# ATmega_Motherboard.net
KiCad netlist of a schematic drawn in Altium Designer
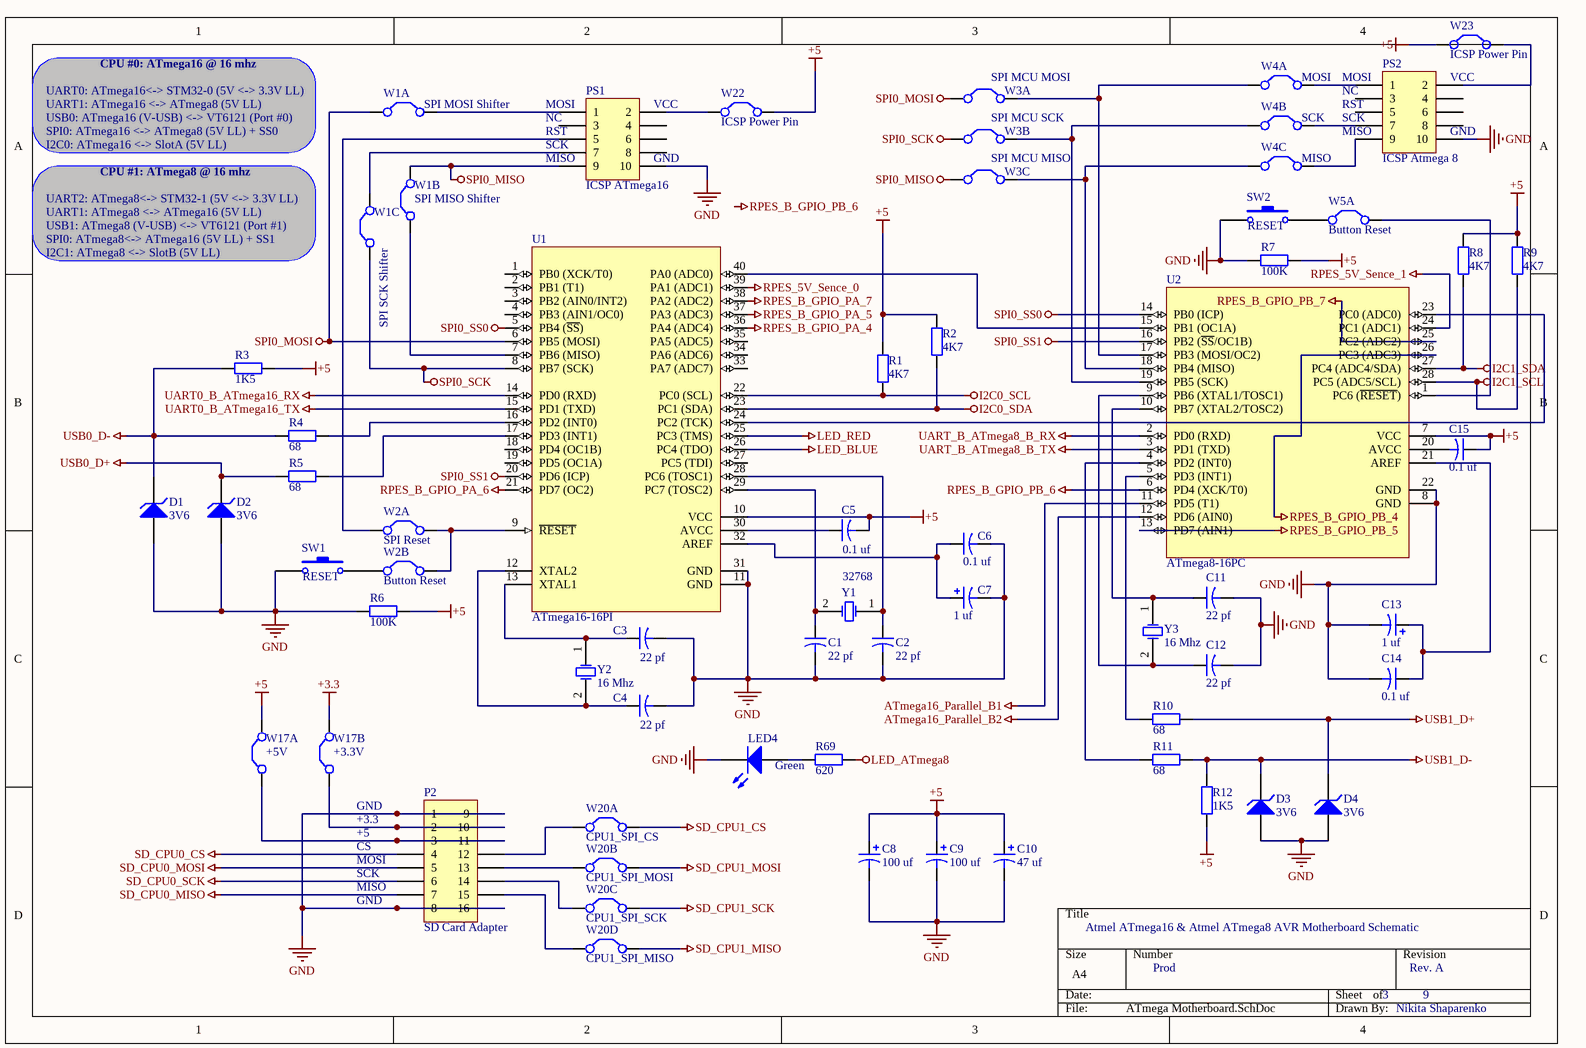
[diagram p0: ATmega Motherboard.SchDoc]

(export (version "E")
  (design (tool "Eeschema 10.0.6"))
  (components
    (comp (ref "C1")
      (value "22 pf")
      (footprint "CAPR5-4X5")
      (description "Capacitor")
      (fields (field (name "Comment") "Cap2") (field (name "PUBLISHER") "Altium Limited"))
      (libsource (lib "Miscellaneous Devices") (part "Cap2"))
    )
    (comp (ref "C2")
      (value "22 pf")
      (footprint "CAPR5-4X5")
      (description "Capacitor")
      (fields (field (name "Comment") "Cap2") (field (name "PUBLISHER") "Altium Limited"))
      (libsource (lib "Miscellaneous Devices") (part "Cap2"))
    )
    (comp (ref "C3")
      (value "22 pf")
      (footprint "CAPR5-4X5")
      (description "Capacitor")
      (fields (field (name "Comment") "Cap2") (field (name "PUBLISHER") "Altium Limited"))
      (libsource (lib "Miscellaneous Devices") (part "Cap2"))
    )
    (comp (ref "C4")
      (value "22 pf")
      (footprint "CAPR5-4X5")
      (description "Capacitor")
      (fields (field (name "Comment") "Cap2") (field (name "PUBLISHER") "Altium Limited"))
      (libsource (lib "Miscellaneous Devices") (part "Cap2"))
    )
    (comp (ref "C5")
      (value "0.1 uf")
      (footprint "CAPR5-4X5")
      (description "Capacitor")
      (fields (field (name "Comment") "Cap2") (field (name "PUBLISHER") "Altium Limited"))
      (libsource (lib "Miscellaneous Devices") (part "Cap2"))
    )
    (comp (ref "C6")
      (value "0.1 uf")
      (footprint "CAPR5-4X5")
      (description "Capacitor")
      (fields (field (name "Comment") "Cap2") (field (name "PUBLISHER") "Altium Limited"))
      (libsource (lib "Miscellaneous Devices") (part "Cap2"))
    )
    (comp (ref "C7")
      (value "1 uf")
      (footprint "RAD-0.2")
      (description "Polarized Capacitor (Radial)")
      (fields (field (name "Comment") "Cap Pol1") (field (name "PUBLISHER") "Altium Limited"))
      (libsource (lib "Miscellaneous Devices") (part "Cap Pol1"))
    )
    (comp (ref "C8")
      (value "100 uf")
      (footprint "RAD-0.2")
      (description "Polarized Capacitor (Radial)")
      (fields (field (name "Comment") "Cap Pol1") (field (name "PUBLISHER") "Altium Limited"))
      (libsource (lib "Miscellaneous Devices") (part "Cap Pol1"))
    )
    (comp (ref "C9")
      (value "100 uf")
      (footprint "RAD-0.2")
      (description "Polarized Capacitor (Radial)")
      (fields (field (name "Comment") "Cap Pol1") (field (name "PUBLISHER") "Altium Limited"))
      (libsource (lib "Miscellaneous Devices") (part "Cap Pol1"))
    )
    (comp (ref "C10")
      (value "47 uf")
      (footprint "RAD-0.2")
      (description "Polarized Capacitor (Radial)")
      (fields (field (name "Comment") "Cap Pol1") (field (name "PUBLISHER") "Altium Limited"))
      (libsource (lib "Miscellaneous Devices") (part "Cap Pol1"))
    )
    (comp (ref "C11")
      (value "22 pf")
      (footprint "CAPR5-4X5")
      (description "Capacitor")
      (fields (field (name "Comment") "Cap2") (field (name "PUBLISHER") "Altium Limited"))
      (libsource (lib "Miscellaneous Devices") (part "Cap2"))
    )
    (comp (ref "C12")
      (value "22 pf")
      (footprint "CAPR5-4X5")
      (description "Capacitor")
      (fields (field (name "Comment") "Cap2") (field (name "PUBLISHER") "Altium Limited"))
      (libsource (lib "Miscellaneous Devices") (part "Cap2"))
    )
    (comp (ref "C13")
      (value "1 uf")
      (footprint "RAD-0.2")
      (description "Polarized Capacitor (Radial)")
      (fields (field (name "Comment") "Cap Pol1") (field (name "PUBLISHER") "Altium Limited"))
      (libsource (lib "Miscellaneous Devices") (part "Cap Pol1"))
    )
    (comp (ref "C14")
      (value "0.1 uf")
      (footprint "CAPR5-4X5")
      (description "Capacitor")
      (fields (field (name "Comment") "Cap2") (field (name "PUBLISHER") "Altium Limited"))
      (libsource (lib "Miscellaneous Devices") (part "Cap2"))
    )
    (comp (ref "C15")
      (value "0.1 uf")
      (footprint "CAPR5-4X5")
      (description "Capacitor")
      (fields (field (name "Comment") "Cap2") (field (name "PUBLISHER") "Altium Limited"))
      (libsource (lib "Miscellaneous Devices") (part "Cap2"))
    )
    (comp (ref "D1")
      (value "3V6")
      (footprint "DIODE-0.7")
      (description "Zener Diode")
      (fields (field (name "PUBLISHER") "Altium Limited"))
      (libsource (lib "Miscellaneous Devices") (part "D Zener"))
    )
    (comp (ref "D2")
      (value "3V6")
      (footprint "DIODE-0.7")
      (description "Zener Diode")
      (fields (field (name "PUBLISHER") "Altium Limited"))
      (libsource (lib "Miscellaneous Devices") (part "D Zener"))
    )
    (comp (ref "D3")
      (value "3V6")
      (footprint "DIODE-0.7")
      (description "Zener Diode")
      (fields (field (name "PUBLISHER") "Altium Limited"))
      (libsource (lib "Miscellaneous Devices") (part "D Zener"))
    )
    (comp (ref "D4")
      (value "3V6")
      (footprint "DIODE-0.7")
      (description "Zener Diode")
      (fields (field (name "PUBLISHER") "Altium Limited"))
      (libsource (lib "Miscellaneous Devices") (part "D Zener"))
    )
    (comp (ref "LED4")
      (value "Green")
      (footprint "LED-1")
      (description "Typical RED GaAs LED")
      (fields (field (name "PUBLISHER") "Altium Limited"))
      (libsource (lib "Miscellaneous Devices") (part "LED1"))
    )
    (comp (ref "P2")
      (value "SD Card Adapter")
      (footprint "HDR2X8_CEN")
      (description "Header, 8-Pin, Dual row")
      (fields (field (name "PUBLISHER") "Altium Limited"))
      (libsource (lib "Miscellaneous Connectors") (part "Header 8X2A"))
    )
    (comp (ref "PS1")
      (value "ICSP ATmega16")
      (footprint "HDR2X5")
      (description "Header, 5-Pin, Dual row")
      (fields (field (name "PUBLISHER") "Altium Limited"))
      (libsource (lib "Miscellaneous Connectors") (part "Header 5X2"))
    )
    (comp (ref "PS2")
      (value "ICSP Atmega 8")
      (footprint "HDR2X5")
      (description "Header, 5-Pin, Dual row")
      (fields (field (name "PUBLISHER") "Altium Limited"))
      (libsource (lib "Miscellaneous Connectors") (part "Header 5X2"))
    )
    (comp (ref "R1")
      (value "4K7")
      (footprint "AXIAL-0.4")
      (description "Resistor")
      (fields (field (name "Comment") "Res2") (field (name "PUBLISHER") "Altium Limited"))
      (libsource (lib "") (part "Res2_1"))
    )
    (comp (ref "R2")
      (value "4K7")
      (footprint "AXIAL-0.4")
      (description "Resistor")
      (fields (field (name "Comment") "Res2") (field (name "PUBLISHER") "Altium Limited"))
      (libsource (lib "") (part "Res2_1"))
    )
    (comp (ref "R3")
      (value "1K5")
      (footprint "AXIAL-0.4")
      (description "Resistor")
      (fields (field (name "Comment") "Res2") (field (name "PUBLISHER") "Altium Limited"))
      (libsource (lib "Miscellaneous Devices") (part "Res2"))
    )
    (comp (ref "R4")
      (value "68")
      (footprint "AXIAL-0.4")
      (description "Resistor")
      (fields (field (name "Comment") "Res2") (field (name "PUBLISHER") "Altium Limited"))
      (libsource (lib "Miscellaneous Devices") (part "Res2"))
    )
    (comp (ref "R5")
      (value "68")
      (footprint "AXIAL-0.4")
      (description "Resistor")
      (fields (field (name "Comment") "Res2") (field (name "PUBLISHER") "Altium Limited"))
      (libsource (lib "Miscellaneous Devices") (part "Res2"))
    )
    (comp (ref "R6")
      (value "100K")
      (footprint "AXIAL-0.4")
      (description "Resistor")
      (fields (field (name "Comment") "Res2") (field (name "PUBLISHER") "Altium Limited"))
      (libsource (lib "Miscellaneous Devices") (part "Res2"))
    )
    (comp (ref "R7")
      (value "100K")
      (footprint "AXIAL-0.4")
      (description "Resistor")
      (fields (field (name "Comment") "Res2") (field (name "PUBLISHER") "Altium Limited"))
      (libsource (lib "Miscellaneous Devices") (part "Res2"))
    )
    (comp (ref "R8")
      (value "4K7")
      (footprint "AXIAL-0.4")
      (description "Resistor")
      (fields (field (name "Comment") "Res2") (field (name "PUBLISHER") "Altium Limited"))
      (libsource (lib "") (part "Res2_1"))
    )
    (comp (ref "R9")
      (value "4K7")
      (footprint "AXIAL-0.4")
      (description "Resistor")
      (fields (field (name "Comment") "Res2") (field (name "PUBLISHER") "Altium Limited"))
      (libsource (lib "") (part "Res2_1"))
    )
    (comp (ref "R10")
      (value "68")
      (footprint "AXIAL-0.4")
      (description "Resistor")
      (fields (field (name "Comment") "Res2") (field (name "PUBLISHER") "Altium Limited"))
      (libsource (lib "") (part "Res2_2"))
    )
    (comp (ref "R11")
      (value "68")
      (footprint "AXIAL-0.4")
      (description "Resistor")
      (fields (field (name "Comment") "Res2") (field (name "PUBLISHER") "Altium Limited"))
      (libsource (lib "") (part "Res2_2"))
    )
    (comp (ref "R12")
      (value "1K5")
      (footprint "AXIAL-0.4")
      (description "Resistor")
      (fields (field (name "Comment") "Res2") (field (name "PUBLISHER") "Altium Limited"))
      (libsource (lib "") (part "Res2_1"))
    )
    (comp (ref "R69")
      (value "620")
      (footprint "AXIAL-0.4")
      (description "Resistor")
      (fields (field (name "Comment") "Res2") (field (name "PUBLISHER") "Altium Limited"))
      (libsource (lib "") (part "Res2_2"))
    )
    (comp (ref "SW1")
      (value "RESET")
      (footprint "SPST-2")
      (description "Switch")
      (fields (field (name "PUBLISHER") "Altium Limited"))
      (libsource (lib "Miscellaneous Devices") (part "SW-PB"))
    )
    (comp (ref "SW2")
      (value "RESET")
      (footprint "SPST-2")
      (description "Switch")
      (fields (field (name "PUBLISHER") "Altium Limited"))
      (libsource (lib "Miscellaneous Devices") (part "SW-PB"))
    )
    (comp (ref "U1")
      (value "ATmega16-16PI")
      (footprint "40P6")
      (description "8-Bit AVR Microcontroller with 16K Bytes of In-System Programmable Flash Memory")
      (fields (field (name "PUBLISHER") "Altium Limited"))
      (libsource (lib "Atmel Microcontroller 8-Bit AVR") (part "ATmega16-16PI"))
    )
    (comp (ref "U2")
      (value "ATmega8-16PC")
      (footprint "28P3")
      (description "8-Bit AVR Microcontroller with 8K Bytes of In-System Programmable Flash Memory")
      (fields (field (name "PUBLISHER") "Altium Limited"))
      (libsource (lib "Atmel Microcontroller 8-Bit AVR") (part "ATmega8-16PC"))
    )
    (comp (ref "W1A")
      (value "SPI MOSI Shifter")
      (footprint "RAD-0.1")
      (description "Jumper Wire")
      (fields (field (name "PUBLISHER") "Altium Limited"))
      (libsource (lib "Miscellaneous Devices") (part "Jumper"))
    )
    (comp (ref "W1B")
      (value "SPI MISO Shifter")
      (footprint "RAD-0.1")
      (description "Jumper Wire")
      (fields (field (name "PUBLISHER") "Altium Limited"))
      (libsource (lib "Miscellaneous Devices") (part "Jumper"))
    )
    (comp (ref "W1C")
      (value "SPI SCK Shifter")
      (footprint "RAD-0.1")
      (description "Jumper Wire")
      (fields (field (name "PUBLISHER") "Altium Limited"))
      (libsource (lib "Miscellaneous Devices") (part "Jumper"))
    )
    (comp (ref "W2A")
      (value "SPI Reset")
      (footprint "RAD-0.1")
      (description "Jumper Wire")
      (fields (field (name "PUBLISHER") "Altium Limited"))
      (libsource (lib "Miscellaneous Devices") (part "Jumper"))
    )
    (comp (ref "W2B")
      (value "Button Reset")
      (footprint "RAD-0.1")
      (description "Jumper Wire")
      (fields (field (name "PUBLISHER") "Altium Limited"))
      (libsource (lib "Miscellaneous Devices") (part "Jumper"))
    )
    (comp (ref "W3A")
      (value "SPI MCU MOSI")
      (footprint "RAD-0.1")
      (description "Jumper Wire")
      (fields (field (name "PUBLISHER") "Altium Limited"))
      (libsource (lib "Miscellaneous Devices") (part "Jumper"))
    )
    (comp (ref "W3B")
      (value "SPI MCU SCK")
      (footprint "RAD-0.1")
      (description "Jumper Wire")
      (fields (field (name "PUBLISHER") "Altium Limited"))
      (libsource (lib "Miscellaneous Devices") (part "Jumper"))
    )
    (comp (ref "W3C")
      (value "SPI MCU MISO")
      (footprint "RAD-0.1")
      (description "Jumper Wire")
      (fields (field (name "PUBLISHER") "Altium Limited"))
      (libsource (lib "Miscellaneous Devices") (part "Jumper"))
    )
    (comp (ref "W4A")
      (value "MOSI")
      (footprint "RAD-0.1")
      (description "Jumper Wire")
      (fields (field (name "PUBLISHER") "Altium Limited"))
      (libsource (lib "Miscellaneous Devices") (part "Jumper"))
    )
    (comp (ref "W4B")
      (value "SCK")
      (footprint "RAD-0.1")
      (description "Jumper Wire")
      (fields (field (name "PUBLISHER") "Altium Limited"))
      (libsource (lib "Miscellaneous Devices") (part "Jumper"))
    )
    (comp (ref "W4C")
      (value "MISO")
      (footprint "RAD-0.2")
      (description "Jumper Wire")
      (fields (field (name "PUBLISHER") "Altium Limited"))
      (libsource (lib "Miscellaneous Devices") (part "Jumper"))
    )
    (comp (ref "W5A")
      (value "Button Reset")
      (footprint "RAD-0.1")
      (description "Jumper Wire")
      (fields (field (name "PUBLISHER") "Altium Limited"))
      (libsource (lib "Miscellaneous Devices") (part "Jumper"))
    )
    (comp (ref "W17A")
      (value "+5V")
      (footprint "RAD-0.1")
      (description "Jumper Wire")
      (fields (field (name "PUBLISHER") "Altium Limited"))
      (libsource (lib "Miscellaneous Devices") (part "Jumper"))
    )
    (comp (ref "W17B")
      (value "+3.3V")
      (footprint "RAD-0.1")
      (description "Jumper Wire")
      (fields (field (name "PUBLISHER") "Altium Limited"))
      (libsource (lib "Miscellaneous Devices") (part "Jumper"))
    )
    (comp (ref "W20A")
      (value "CPU1_SPI_CS")
      (footprint "RAD-0.1")
      (description "Jumper Wire")
      (fields (field (name "PUBLISHER") "Altium Limited"))
      (libsource (lib "Miscellaneous Devices") (part "Jumper"))
    )
    (comp (ref "W20B")
      (value "CPU1_SPI_MOSI")
      (footprint "RAD-0.1")
      (description "Jumper Wire")
      (fields (field (name "PUBLISHER") "Altium Limited"))
      (libsource (lib "Miscellaneous Devices") (part "Jumper"))
    )
    (comp (ref "W20C")
      (value "CPU1_SPI_SCK")
      (footprint "RAD-0.1")
      (description "Jumper Wire")
      (fields (field (name "PUBLISHER") "Altium Limited"))
      (libsource (lib "Miscellaneous Devices") (part "Jumper"))
    )
    (comp (ref "W20D")
      (value "CPU1_SPI_MISO")
      (footprint "RAD-0.1")
      (description "Jumper Wire")
      (fields (field (name "PUBLISHER") "Altium Limited"))
      (libsource (lib "Miscellaneous Devices") (part "Jumper"))
    )
    (comp (ref "W22")
      (value "ICSP Power Pin")
      (footprint "RAD-0.1")
      (description "Jumper Wire")
      (fields (field (name "PUBLISHER") "Altium Limited"))
      (libsource (lib "Miscellaneous Devices") (part "Jumper"))
    )
    (comp (ref "W23")
      (value "ICSP Power Pin")
      (footprint "RAD-0.1")
      (description "Jumper Wire")
      (fields (field (name "PUBLISHER") "Altium Limited"))
      (libsource (lib "Miscellaneous Devices") (part "Jumper"))
    )
    (comp (ref "Y1")
      (value "32768")
      (footprint "R38")
      (description "Crystal Oscillator")
      (fields (field (name "PUBLISHER") "Altium Limited"))
      (libsource (lib "Miscellaneous Devices") (part "XTAL"))
    )
    (comp (ref "Y2")
      (value "16 Mhz")
      (footprint "R38")
      (description "Crystal Oscillator")
      (fields (field (name "PUBLISHER") "Altium Limited"))
      (libsource (lib "Miscellaneous Devices") (part "XTAL"))
    )
    (comp (ref "Y3")
      (value "16 Mhz")
      (footprint "R38")
      (description "Crystal Oscillator")
      (fields (field (name "PUBLISHER") "Altium Limited"))
      (libsource (lib "Miscellaneous Devices") (part "XTAL"))
    )
  )
  (nets
    (net (code "1") (name "+3.3") (class "Default")
      (node (ref "W17B") (pin "2") (pinfunction "C2_2") (pintype "passive"))
    )
    (net (code "2") (name "+5") (class "Default")
      (node (ref "C10") (pin "1") (pinfunction "1_1") (pintype "passive"))
      (node (ref "C15") (pin "1") (pinfunction "1_1") (pintype "passive"))
      (node (ref "C5") (pin "2") (pinfunction "2_2") (pintype "passive"))
      (node (ref "C8") (pin "1") (pinfunction "1_1") (pintype "passive"))
      (node (ref "C9") (pin "1") (pinfunction "1_1") (pintype "passive"))
      (node (ref "R1") (pin "1") (pinfunction "1_1") (pintype "passive"))
      (node (ref "R12") (pin "2") (pinfunction "2_2") (pintype "passive"))
      (node (ref "R2") (pin "1") (pinfunction "1_1") (pintype "passive"))
      (node (ref "R3") (pin "1") (pinfunction "1_1") (pintype "passive"))
      (node (ref "R6") (pin "1") (pinfunction "1_1") (pintype "passive"))
      (node (ref "R7") (pin "1") (pinfunction "1_1") (pintype "passive"))
      (node (ref "R8") (pin "1") (pinfunction "1_1") (pintype "passive"))
      (node (ref "R9") (pin "1") (pinfunction "1_1") (pintype "passive"))
      (node (ref "U1") (pin "10") (pinfunction "VCC_10") (pintype "power_in"))
      (node (ref "U2") (pin "7") (pinfunction "VCC_7") (pintype "power_in"))
      (node (ref "W17A") (pin "2") (pinfunction "C2_2") (pintype "passive"))
      (node (ref "W22") (pin "2") (pinfunction "C2_2") (pintype "passive"))
      (node (ref "W23") (pin "1") (pinfunction "C1_1") (pintype "passive"))
    )
    (net (code "3") (name "ATmega16_Parallel_B1") (class "Default")
      (node (ref "U2") (pin "11") (pinfunction "PD5_(T1)_11") (pintype "bidirectional"))
    )
    (net (code "4") (name "ATmega16_Parallel_B2") (class "Default")
      (node (ref "U2") (pin "12") (pinfunction "PD6_(AIN0)_12") (pintype "bidirectional"))
    )
    (net (code "5") (name "GND") (class "Default")
      (node (ref "C1") (pin "2") (pinfunction "2_2") (pintype "passive"))
      (node (ref "C10") (pin "2") (pinfunction "2_2") (pintype "passive"))
      (node (ref "C11") (pin "2") (pinfunction "2_2") (pintype "passive"))
      (node (ref "C12") (pin "2") (pinfunction "2_2") (pintype "passive"))
      (node (ref "C13") (pin "2") (pinfunction "2_2") (pintype "passive"))
      (node (ref "C14") (pin "2") (pinfunction "2_2") (pintype "passive"))
      (node (ref "C2") (pin "2") (pinfunction "2_2") (pintype "passive"))
      (node (ref "C3") (pin "2") (pinfunction "2_2") (pintype "passive"))
      (node (ref "C4") (pin "2") (pinfunction "2_2") (pintype "passive"))
      (node (ref "C6") (pin "2") (pinfunction "2_2") (pintype "passive"))
      (node (ref "C7") (pin "2") (pinfunction "2_2") (pintype "passive"))
      (node (ref "C8") (pin "2") (pinfunction "2_2") (pintype "passive"))
      (node (ref "C9") (pin "2") (pinfunction "2_2") (pintype "passive"))
      (node (ref "D1") (pin "1") (pinfunction "A_1") (pintype "passive"))
      (node (ref "D2") (pin "1") (pinfunction "A_1") (pintype "passive"))
      (node (ref "D3") (pin "1") (pinfunction "A_1") (pintype "passive"))
      (node (ref "D4") (pin "1") (pinfunction "A_1") (pintype "passive"))
      (node (ref "LED4") (pin "2") (pinfunction "K_2") (pintype "passive"))
      (node (ref "P2") (pin "1") (pinfunction "1_1") (pintype "passive"))
      (node (ref "P2") (pin "16") (pinfunction "16_16") (pintype "passive"))
      (node (ref "P2") (pin "8") (pinfunction "8_8") (pintype "passive"))
      (node (ref "P2") (pin "9") (pinfunction "9_9") (pintype "passive"))
      (node (ref "PS1") (pin "10") (pinfunction "10_10") (pintype "passive"))
      (node (ref "PS2") (pin "10") (pinfunction "10_10") (pintype "passive"))
      (node (ref "R6") (pin "2") (pinfunction "2_2") (pintype "passive"))
      (node (ref "R7") (pin "2") (pinfunction "2_2") (pintype "passive"))
      (node (ref "SW1") (pin "1") (pinfunction "1_1") (pintype "passive"))
      (node (ref "SW2") (pin "1") (pinfunction "1_1") (pintype "passive"))
      (node (ref "U1") (pin "11") (pinfunction "GND_11") (pintype "power_in"))
      (node (ref "U1") (pin "31") (pinfunction "GND_31") (pintype "power_in"))
      (node (ref "U2") (pin "22") (pinfunction "GND_22") (pintype "power_in"))
      (node (ref "U2") (pin "8") (pinfunction "GND_8") (pintype "power_in"))
    )
    (net (code "6") (name "I2C0_SCL") (class "Default")
      (node (ref "R1") (pin "2") (pinfunction "2_2") (pintype "passive"))
      (node (ref "U1") (pin "22") (pinfunction "PC0_(SCL)_22") (pintype "bidirectional"))
    )
    (net (code "7") (name "I2C0_SDA") (class "Default")
      (node (ref "R2") (pin "2") (pinfunction "2_2") (pintype "passive"))
      (node (ref "U1") (pin "23") (pinfunction "PC1_(SDA)_23") (pintype "bidirectional"))
    )
    (net (code "8") (name "I2C1_SCL") (class "Default")
      (node (ref "R9") (pin "2") (pinfunction "2_2") (pintype "passive"))
      (node (ref "U2") (pin "28") (pinfunction "PC5_(ADC5/SCL)_28") (pintype "bidirectional"))
    )
    (net (code "9") (name "I2C1_SDA") (class "Default")
      (node (ref "R8") (pin "2") (pinfunction "2_2") (pintype "passive"))
      (node (ref "U2") (pin "27") (pinfunction "PC4_(ADC4/SDA)_27") (pintype "bidirectional"))
    )
    (net (code "10") (name "LED_ATmega8") (class "Default")
      (node (ref "R69") (pin "2") (pinfunction "2_2") (pintype "passive"))
    )
    (net (code "11") (name "LED_BLUE") (class "Default")
      (node (ref "U1") (pin "26") (pinfunction "PC4_(TDO)_26") (pintype "bidirectional"))
    )
    (net (code "12") (name "LED_RED") (class "Default")
      (node (ref "U1") (pin "25") (pinfunction "PC3_(TMS)_25") (pintype "bidirectional"))
    )
    (net (code "13") (name "Net-(LED4-A)") (class "Default")
      (node (ref "LED4") (pin "1") (pinfunction "A_1") (pintype "passive"))
      (node (ref "R69") (pin "1") (pinfunction "1_1") (pintype "passive"))
    )
    (net (code "14") (name "Net-(U1-AREF)") (class "Default")
      (node (ref "C6") (pin "1") (pinfunction "1_1") (pintype "passive"))
      (node (ref "C7") (pin "1") (pinfunction "1_1") (pintype "passive"))
      (node (ref "U1") (pin "32") (pinfunction "AREF_32") (pintype "passive"))
    )
    (net (code "15") (name "Net-(U1-AVCC)") (class "Default")
      (node (ref "C5") (pin "1") (pinfunction "1_1") (pintype "passive"))
      (node (ref "U1") (pin "30") (pinfunction "AVCC_30") (pintype "power_in"))
    )
    (net (code "16") (name "Net-(U1-PA0_(ADC0))") (class "Default")
      (node (ref "U1") (pin "40") (pinfunction "PA0_(ADC0)_40") (pintype "bidirectional"))
      (node (ref "U2") (pin "15") (pinfunction "PB1_(OC1A)_15") (pintype "bidirectional"))
    )
    (net (code "17") (name "Net-(U1-PB6_(MISO))") (class "Default")
      (node (ref "U1") (pin "7") (pinfunction "PB6_(MISO)_7") (pintype "bidirectional"))
      (node (ref "W1B") (pin "1") (pinfunction "C1_1") (pintype "passive"))
    )
    (net (code "18") (name "Net-(U1-PC2_(TCK))") (class "Default")
      (node (ref "U1") (pin "24") (pinfunction "PC2_(TCK)_24") (pintype "bidirectional"))
      (node (ref "U2") (pin "23") (pinfunction "PC0_(ADC0)_23") (pintype "bidirectional"))
    )
    (net (code "19") (name "Net-(U1-PC6_(TOSC1))") (class "Default")
      (node (ref "C2") (pin "1") (pinfunction "1_1") (pintype "passive"))
      (node (ref "U1") (pin "28") (pinfunction "PC6_(TOSC1)_28") (pintype "bidirectional"))
      (node (ref "Y1") (pin "1") (pinfunction "OSC1_1") (pintype "passive"))
    )
    (net (code "20") (name "Net-(U1-PC7_(TOSC2))") (class "Default")
      (node (ref "C1") (pin "1") (pinfunction "1_1") (pintype "passive"))
      (node (ref "U1") (pin "29") (pinfunction "PC7_(TOSC2)_29") (pintype "bidirectional"))
      (node (ref "Y1") (pin "2") (pinfunction "OSC2_2") (pintype "passive"))
    )
    (net (code "21") (name "Net-(U1-PD2_(INT0))") (class "Default")
      (node (ref "R4") (pin "1") (pinfunction "1_1") (pintype "passive"))
      (node (ref "U1") (pin "16") (pinfunction "PD2_(INT0)_16") (pintype "bidirectional"))
    )
    (net (code "22") (name "Net-(U1-PD3_(INT1))") (class "Default")
      (node (ref "R5") (pin "1") (pinfunction "1_1") (pintype "passive"))
      (node (ref "U1") (pin "17") (pinfunction "PD3_(INT1)_17") (pintype "bidirectional"))
    )
    (net (code "23") (name "Net-(U1-XTAL1)") (class "Default")
      (node (ref "C3") (pin "1") (pinfunction "1_1") (pintype "passive"))
      (node (ref "U1") (pin "13") (pinfunction "XTAL1_13") (pintype "passive"))
      (node (ref "Y2") (pin "1") (pinfunction "OSC1_1") (pintype "passive"))
    )
    (net (code "24") (name "Net-(U1-XTAL2)") (class "Default")
      (node (ref "C4") (pin "1") (pinfunction "1_1") (pintype "passive"))
      (node (ref "U1") (pin "12") (pinfunction "XTAL2_12") (pintype "passive"))
      (node (ref "Y2") (pin "2") (pinfunction "OSC2_2") (pintype "passive"))
    )
    (net (code "25") (name "Net-(U1-~{RESET})") (class "Default")
      (node (ref "U1") (pin "9") (pinfunction "~{RESET}_9") (pintype "input"))
      (node (ref "W2A") (pin "2") (pinfunction "C2_2") (pintype "passive"))
      (node (ref "W2B") (pin "2") (pinfunction "C2_2") (pintype "passive"))
    )
    (net (code "26") (name "Net-(U2-AREF)") (class "Default")
      (node (ref "C13") (pin "1") (pinfunction "1_1") (pintype "passive"))
      (node (ref "C14") (pin "1") (pinfunction "1_1") (pintype "passive"))
      (node (ref "U2") (pin "21") (pinfunction "AREF_21") (pintype "passive"))
    )
    (net (code "27") (name "Net-(U2-AVCC)") (class "Default")
      (node (ref "C15") (pin "2") (pinfunction "2_2") (pintype "passive"))
      (node (ref "U2") (pin "20") (pinfunction "AVCC_20") (pintype "power_in"))
    )
    (net (code "28") (name "Net-(U2-PB3_(MOSI{slash}OC2))") (class "Default")
      (node (ref "U2") (pin "17") (pinfunction "PB3_(MOSI/OC2)_17") (pintype "bidirectional"))
      (node (ref "W3A") (pin "2") (pinfunction "C2_2") (pintype "passive"))
      (node (ref "W4A") (pin "1") (pinfunction "C1_1") (pintype "passive"))
    )
    (net (code "29") (name "Net-(U2-PB4_(MISO))") (class "Default")
      (node (ref "U2") (pin "18") (pinfunction "PB4_(MISO)_18") (pintype "bidirectional"))
      (node (ref "W3C") (pin "2") (pinfunction "C2_2") (pintype "passive"))
      (node (ref "W4C") (pin "1") (pinfunction "C1_1") (pintype "passive"))
    )
    (net (code "30") (name "Net-(U2-PB5_(SCK))") (class "Default")
      (node (ref "U2") (pin "19") (pinfunction "PB5_(SCK)_19") (pintype "bidirectional"))
      (node (ref "W3B") (pin "2") (pinfunction "C2_2") (pintype "passive"))
      (node (ref "W4B") (pin "1") (pinfunction "C1_1") (pintype "passive"))
    )
    (net (code "31") (name "Net-(U2-PB6_(XTAL1{slash}TOSC1))") (class "Default")
      (node (ref "C12") (pin "1") (pinfunction "1_1") (pintype "passive"))
      (node (ref "U2") (pin "9") (pinfunction "PB6_(XTAL1/TOSC1)_9") (pintype "bidirectional"))
      (node (ref "Y3") (pin "2") (pinfunction "OSC2_2") (pintype "passive"))
    )
    (net (code "32") (name "Net-(U2-PB7_(XTAL2{slash}TOSC2))") (class "Default")
      (node (ref "C11") (pin "1") (pinfunction "1_1") (pintype "passive"))
      (node (ref "U2") (pin "10") (pinfunction "PB7_(XTAL2/TOSC2)_10") (pintype "bidirectional"))
      (node (ref "Y3") (pin "1") (pinfunction "OSC1_1") (pintype "passive"))
    )
    (net (code "33") (name "Net-(U2-PC6_(~{RESET}))") (class "Default")
      (node (ref "U2") (pin "1") (pinfunction "PC6_(~{RESET})_1") (pintype "bidirectional"))
      (node (ref "W5A") (pin "2") (pinfunction "C2_2") (pintype "passive"))
    )
    (net (code "34") (name "Net-(U2-PD2_(INT0))") (class "Default")
      (node (ref "R11") (pin "1") (pinfunction "1_1") (pintype "passive"))
      (node (ref "U2") (pin "4") (pinfunction "PD2_(INT0)_4") (pintype "bidirectional"))
    )
    (net (code "35") (name "Net-(U2-PD3_(INT1))") (class "Default")
      (node (ref "R10") (pin "1") (pinfunction "1_1") (pintype "passive"))
      (node (ref "U2") (pin "5") (pinfunction "PD3_(INT1)_5") (pintype "bidirectional"))
    )
    (net (code "36") (name "Net-(W1A-C2)") (class "Default")
      (node (ref "PS1") (pin "1") (pinfunction "1_1") (pintype "passive"))
      (node (ref "W1A") (pin "2") (pinfunction "C2_2") (pintype "passive"))
    )
    (net (code "37") (name "Net-(W1C-C2)") (class "Default")
      (node (ref "PS1") (pin "7") (pinfunction "7_7") (pintype "passive"))
      (node (ref "W1C") (pin "2") (pinfunction "C2_2") (pintype "passive"))
    )
    (net (code "38") (name "Net-(W2A-C1)") (class "Default")
      (node (ref "PS1") (pin "5") (pinfunction "5_5") (pintype "passive"))
      (node (ref "W2A") (pin "1") (pinfunction "C1_1") (pintype "passive"))
    )
    (net (code "39") (name "Net-(W2B-C1)") (class "Default")
      (node (ref "SW1") (pin "2") (pinfunction "2_2") (pintype "passive"))
      (node (ref "W2B") (pin "1") (pinfunction "C1_1") (pintype "passive"))
    )
    (net (code "40") (name "Net-(W4A-C2)") (class "Default")
      (node (ref "PS2") (pin "1") (pinfunction "1_1") (pintype "passive"))
      (node (ref "W4A") (pin "2") (pinfunction "C2_2") (pintype "passive"))
    )
    (net (code "41") (name "Net-(W4B-C2)") (class "Default")
      (node (ref "PS2") (pin "7") (pinfunction "7_7") (pintype "passive"))
      (node (ref "W4B") (pin "2") (pinfunction "C2_2") (pintype "passive"))
    )
    (net (code "42") (name "Net-(W4C-C2)") (class "Default")
      (node (ref "PS2") (pin "9") (pinfunction "9_9") (pintype "passive"))
      (node (ref "W4C") (pin "2") (pinfunction "C2_2") (pintype "passive"))
    )
    (net (code "43") (name "Net-(W5A-C1)") (class "Default")
      (node (ref "SW2") (pin "2") (pinfunction "2_2") (pintype "passive"))
      (node (ref "W5A") (pin "1") (pinfunction "C1_1") (pintype "passive"))
    )
    (net (code "44") (name "Net-(W17A-C1)") (class "Default")
      (node (ref "P2") (pin "11") (pinfunction "11_11") (pintype "passive"))
      (node (ref "P2") (pin "3") (pinfunction "3_3") (pintype "passive"))
      (node (ref "W17A") (pin "1") (pinfunction "C1_1") (pintype "passive"))
    )
    (net (code "45") (name "Net-(W17B-C1)") (class "Default")
      (node (ref "P2") (pin "10") (pinfunction "10_10") (pintype "passive"))
      (node (ref "P2") (pin "2") (pinfunction "2_2") (pintype "passive"))
      (node (ref "W17B") (pin "1") (pinfunction "C1_1") (pintype "passive"))
    )
    (net (code "46") (name "Net-(W20A-C1)") (class "Default")
      (node (ref "P2") (pin "12") (pinfunction "12_12") (pintype "passive"))
      (node (ref "W20A") (pin "1") (pinfunction "C1_1") (pintype "passive"))
    )
    (net (code "47") (name "Net-(W20B-C1)") (class "Default")
      (node (ref "P2") (pin "13") (pinfunction "13_13") (pintype "passive"))
      (node (ref "W20B") (pin "1") (pinfunction "C1_1") (pintype "passive"))
    )
    (net (code "48") (name "Net-(W20C-C1)") (class "Default")
      (node (ref "P2") (pin "14") (pinfunction "14_14") (pintype "passive"))
      (node (ref "W20C") (pin "1") (pinfunction "C1_1") (pintype "passive"))
    )
    (net (code "49") (name "Net-(W20D-C1)") (class "Default")
      (node (ref "P2") (pin "15") (pinfunction "15_15") (pintype "passive"))
      (node (ref "W20D") (pin "1") (pinfunction "C1_1") (pintype "passive"))
    )
    (net (code "50") (name "Net-(W22-C1)") (class "Default")
      (node (ref "PS1") (pin "2") (pinfunction "2_2") (pintype "passive"))
      (node (ref "W22") (pin "1") (pinfunction "C1_1") (pintype "passive"))
    )
    (net (code "51") (name "Net-(W23-C2)") (class "Default")
      (node (ref "PS2") (pin "2") (pinfunction "2_2") (pintype "passive"))
      (node (ref "W23") (pin "2") (pinfunction "C2_2") (pintype "passive"))
    )
    (net (code "52") (name "RPES_5V_Sence_0") (class "Default")
      (node (ref "U1") (pin "39") (pinfunction "PA1_(ADC1)_39") (pintype "bidirectional"))
    )
    (net (code "53") (name "RPES_5V_Sence_1") (class "Default")
      (node (ref "U2") (pin "24") (pinfunction "PC1_(ADC1)_24") (pintype "bidirectional"))
    )
    (net (code "54") (name "RPES_B_GPIO_PA_4") (class "Default")
      (node (ref "U1") (pin "36") (pinfunction "PA4_(ADC4)_36") (pintype "bidirectional"))
    )
    (net (code "55") (name "RPES_B_GPIO_PA_5") (class "Default")
      (node (ref "U1") (pin "37") (pinfunction "PA3_(ADC3)_37") (pintype "bidirectional"))
    )
    (net (code "56") (name "RPES_B_GPIO_PA_6") (class "Default")
      (node (ref "U1") (pin "21") (pinfunction "PD7_(OC2)_21") (pintype "bidirectional"))
    )
    (net (code "57") (name "RPES_B_GPIO_PA_7") (class "Default")
      (node (ref "U1") (pin "38") (pinfunction "PA2_(ADC2)_38") (pintype "bidirectional"))
    )
    (net (code "58") (name "RPES_B_GPIO_PB_4") (class "Default")
      (node (ref "U2") (pin "26") (pinfunction "PC3_(ADC3)_26") (pintype "bidirectional"))
    )
    (net (code "59") (name "RPES_B_GPIO_PB_5") (class "Default")
      (node (ref "U2") (pin "13") (pinfunction "PD7_(AIN1)_13") (pintype "bidirectional"))
    )
    (net (code "60") (name "RPES_B_GPIO_PB_6") (class "Default")
      (node (ref "U2") (pin "6") (pinfunction "PD4_(XCK/T0)_6") (pintype "bidirectional"))
    )
    (net (code "61") (name "RPES_B_GPIO_PB_7") (class "Default")
      (node (ref "U2") (pin "25") (pinfunction "PC2_(ADC2)_25") (pintype "bidirectional"))
    )
    (net (code "62") (name "SD_CPU0_CS") (class "Default")
      (node (ref "P2") (pin "4") (pinfunction "4_4") (pintype "passive"))
    )
    (net (code "63") (name "SD_CPU0_MISO") (class "Default")
      (node (ref "P2") (pin "7") (pinfunction "7_7") (pintype "passive"))
    )
    (net (code "64") (name "SD_CPU0_MOSI") (class "Default")
      (node (ref "P2") (pin "5") (pinfunction "5_5") (pintype "passive"))
    )
    (net (code "65") (name "SD_CPU0_SCK") (class "Default")
      (node (ref "P2") (pin "6") (pinfunction "6_6") (pintype "passive"))
    )
    (net (code "66") (name "SD_CPU1_CS") (class "Default")
      (node (ref "W20A") (pin "2") (pinfunction "C2_2") (pintype "passive"))
    )
    (net (code "67") (name "SD_CPU1_MISO") (class "Default")
      (node (ref "W20D") (pin "2") (pinfunction "C2_2") (pintype "passive"))
    )
    (net (code "68") (name "SD_CPU1_MOSI") (class "Default")
      (node (ref "W20B") (pin "2") (pinfunction "C2_2") (pintype "passive"))
    )
    (net (code "69") (name "SD_CPU1_SCK") (class "Default")
      (node (ref "W20C") (pin "2") (pinfunction "C2_2") (pintype "passive"))
    )
    (net (code "70") (name "SPI0_MISO") (class "Default")
      (node (ref "PS1") (pin "9") (pinfunction "9_9") (pintype "passive"))
      (node (ref "W1B") (pin "2") (pinfunction "C2_2") (pintype "passive"))
      (node (ref "W3C") (pin "1") (pinfunction "C1_1") (pintype "passive"))
    )
    (net (code "71") (name "SPI0_MOSI") (class "Default")
      (node (ref "U1") (pin "6") (pinfunction "PB5_(MOSI)_6") (pintype "bidirectional"))
      (node (ref "W1A") (pin "1") (pinfunction "C1_1") (pintype "passive"))
      (node (ref "W3A") (pin "1") (pinfunction "C1_1") (pintype "passive"))
    )
    (net (code "72") (name "SPI0_SCK") (class "Default")
      (node (ref "U1") (pin "8") (pinfunction "PB7_(SCK)_8") (pintype "bidirectional"))
      (node (ref "W1C") (pin "1") (pinfunction "C1_1") (pintype "passive"))
      (node (ref "W3B") (pin "1") (pinfunction "C1_1") (pintype "passive"))
    )
    (net (code "73") (name "SPI0_SS0") (class "Default")
      (node (ref "U1") (pin "5") (pinfunction "PB4_(~{SS})_5") (pintype "bidirectional"))
      (node (ref "U2") (pin "14") (pinfunction "PB0_(ICP)_14") (pintype "bidirectional"))
    )
    (net (code "74") (name "SPI0_SS1") (class "Default")
      (node (ref "U1") (pin "20") (pinfunction "PD6_(ICP)_20") (pintype "bidirectional"))
      (node (ref "U2") (pin "16") (pinfunction "PB2_(~{SS}/OC1B)_16") (pintype "bidirectional"))
    )
    (net (code "75") (name "UART0_B_ATmega16_RX") (class "Default")
      (node (ref "U1") (pin "14") (pinfunction "PD0_(RXD)_14") (pintype "bidirectional"))
    )
    (net (code "76") (name "UART0_B_ATmega16_TX") (class "Default")
      (node (ref "U1") (pin "15") (pinfunction "PD1_(TXD)_15") (pintype "bidirectional"))
    )
    (net (code "77") (name "UART_B_ATmega8_B_RX") (class "Default")
      (node (ref "U2") (pin "2") (pinfunction "PD0_(RXD)_2") (pintype "bidirectional"))
    )
    (net (code "78") (name "UART_B_ATmega8_B_TX") (class "Default")
      (node (ref "U2") (pin "3") (pinfunction "PD1_(TXD)_3") (pintype "bidirectional"))
    )
    (net (code "79") (name "USB0_D+") (class "Default")
      (node (ref "D2") (pin "2") (pinfunction "K_2") (pintype "passive"))
      (node (ref "R5") (pin "2") (pinfunction "2_2") (pintype "passive"))
    )
    (net (code "80") (name "USB0_D-") (class "Default")
      (node (ref "D1") (pin "2") (pinfunction "K_2") (pintype "passive"))
      (node (ref "R3") (pin "2") (pinfunction "2_2") (pintype "passive"))
      (node (ref "R4") (pin "2") (pinfunction "2_2") (pintype "passive"))
    )
    (net (code "81") (name "USB1_D+") (class "Default")
      (node (ref "D4") (pin "2") (pinfunction "K_2") (pintype "passive"))
      (node (ref "R10") (pin "2") (pinfunction "2_2") (pintype "passive"))
    )
    (net (code "82") (name "USB1_D-") (class "Default")
      (node (ref "D3") (pin "2") (pinfunction "K_2") (pintype "passive"))
      (node (ref "R11") (pin "2") (pinfunction "2_2") (pintype "passive"))
      (node (ref "R12") (pin "1") (pinfunction "1_1") (pintype "passive"))
    )
    (net (code "83") (name "unconnected-(PS1-Pad3)") (class "Default")
      (node (ref "PS1") (pin "3") (pinfunction "3_3") (pintype "passive"))
    )
    (net (code "84") (name "unconnected-(PS1-Pad4)") (class "Default")
      (node (ref "PS1") (pin "4") (pinfunction "4_4") (pintype "passive"))
    )
    (net (code "85") (name "unconnected-(PS1-Pad6)") (class "Default")
      (node (ref "PS1") (pin "6") (pinfunction "6_6") (pintype "passive"))
    )
    (net (code "86") (name "unconnected-(PS1-Pad8)") (class "Default")
      (node (ref "PS1") (pin "8") (pinfunction "8_8") (pintype "passive"))
    )
    (net (code "87") (name "unconnected-(PS2-Pad3)") (class "Default")
      (node (ref "PS2") (pin "3") (pinfunction "3_3") (pintype "passive"))
    )
    (net (code "88") (name "unconnected-(PS2-Pad4)") (class "Default")
      (node (ref "PS2") (pin "4") (pinfunction "4_4") (pintype "passive"))
    )
    (net (code "89") (name "unconnected-(PS2-Pad5)") (class "Default")
      (node (ref "PS2") (pin "5") (pinfunction "5_5") (pintype "passive"))
    )
    (net (code "90") (name "unconnected-(PS2-Pad6)") (class "Default")
      (node (ref "PS2") (pin "6") (pinfunction "6_6") (pintype "passive"))
    )
    (net (code "91") (name "unconnected-(PS2-Pad8)") (class "Default")
      (node (ref "PS2") (pin "8") (pinfunction "8_8") (pintype "passive"))
    )
    (net (code "92") (name "unconnected-(U1-PA5_(ADC5)-Pad35)") (class "Default")
      (node (ref "U1") (pin "35") (pinfunction "PA5_(ADC5)_35") (pintype "bidirectional"))
    )
    (net (code "93") (name "unconnected-(U1-PA6_(ADC6)-Pad34)") (class "Default")
      (node (ref "U1") (pin "34") (pinfunction "PA6_(ADC6)_34") (pintype "bidirectional"))
    )
    (net (code "94") (name "unconnected-(U1-PA7_(ADC7)-Pad33)") (class "Default")
      (node (ref "U1") (pin "33") (pinfunction "PA7_(ADC7)_33") (pintype "bidirectional"))
    )
    (net (code "95") (name "unconnected-(U1-PB0_(XCK{slash}T0)-Pad1)") (class "Default")
      (node (ref "U1") (pin "1") (pinfunction "PB0_(XCK/T0)_1") (pintype "bidirectional"))
    )
    (net (code "96") (name "unconnected-(U1-PB1_(T1)-Pad2)") (class "Default")
      (node (ref "U1") (pin "2") (pinfunction "PB1_(T1)_2") (pintype "bidirectional"))
    )
    (net (code "97") (name "unconnected-(U1-PB2_(AIN0{slash}INT2)-Pad3)") (class "Default")
      (node (ref "U1") (pin "3") (pinfunction "PB2_(AIN0/INT2)_3") (pintype "bidirectional"))
    )
    (net (code "98") (name "unconnected-(U1-PB3_(AIN1{slash}OC0)-Pad4)") (class "Default")
      (node (ref "U1") (pin "4") (pinfunction "PB3_(AIN1/OC0)_4") (pintype "bidirectional"))
    )
    (net (code "99") (name "unconnected-(U1-PC5_(TDI)-Pad27)") (class "Default")
      (node (ref "U1") (pin "27") (pinfunction "PC5_(TDI)_27") (pintype "bidirectional"))
    )
    (net (code "100") (name "unconnected-(U1-PD4_(OC1B)-Pad18)") (class "Default")
      (node (ref "U1") (pin "18") (pinfunction "PD4_(OC1B)_18") (pintype "bidirectional"))
    )
    (net (code "101") (name "unconnected-(U1-PD5_(OC1A)-Pad19)") (class "Default")
      (node (ref "U1") (pin "19") (pinfunction "PD5_(OC1A)_19") (pintype "bidirectional"))
    )
  )
)
